# czbd-v0_12.net
KiCad netlist of a schematic drawn in EAGLE
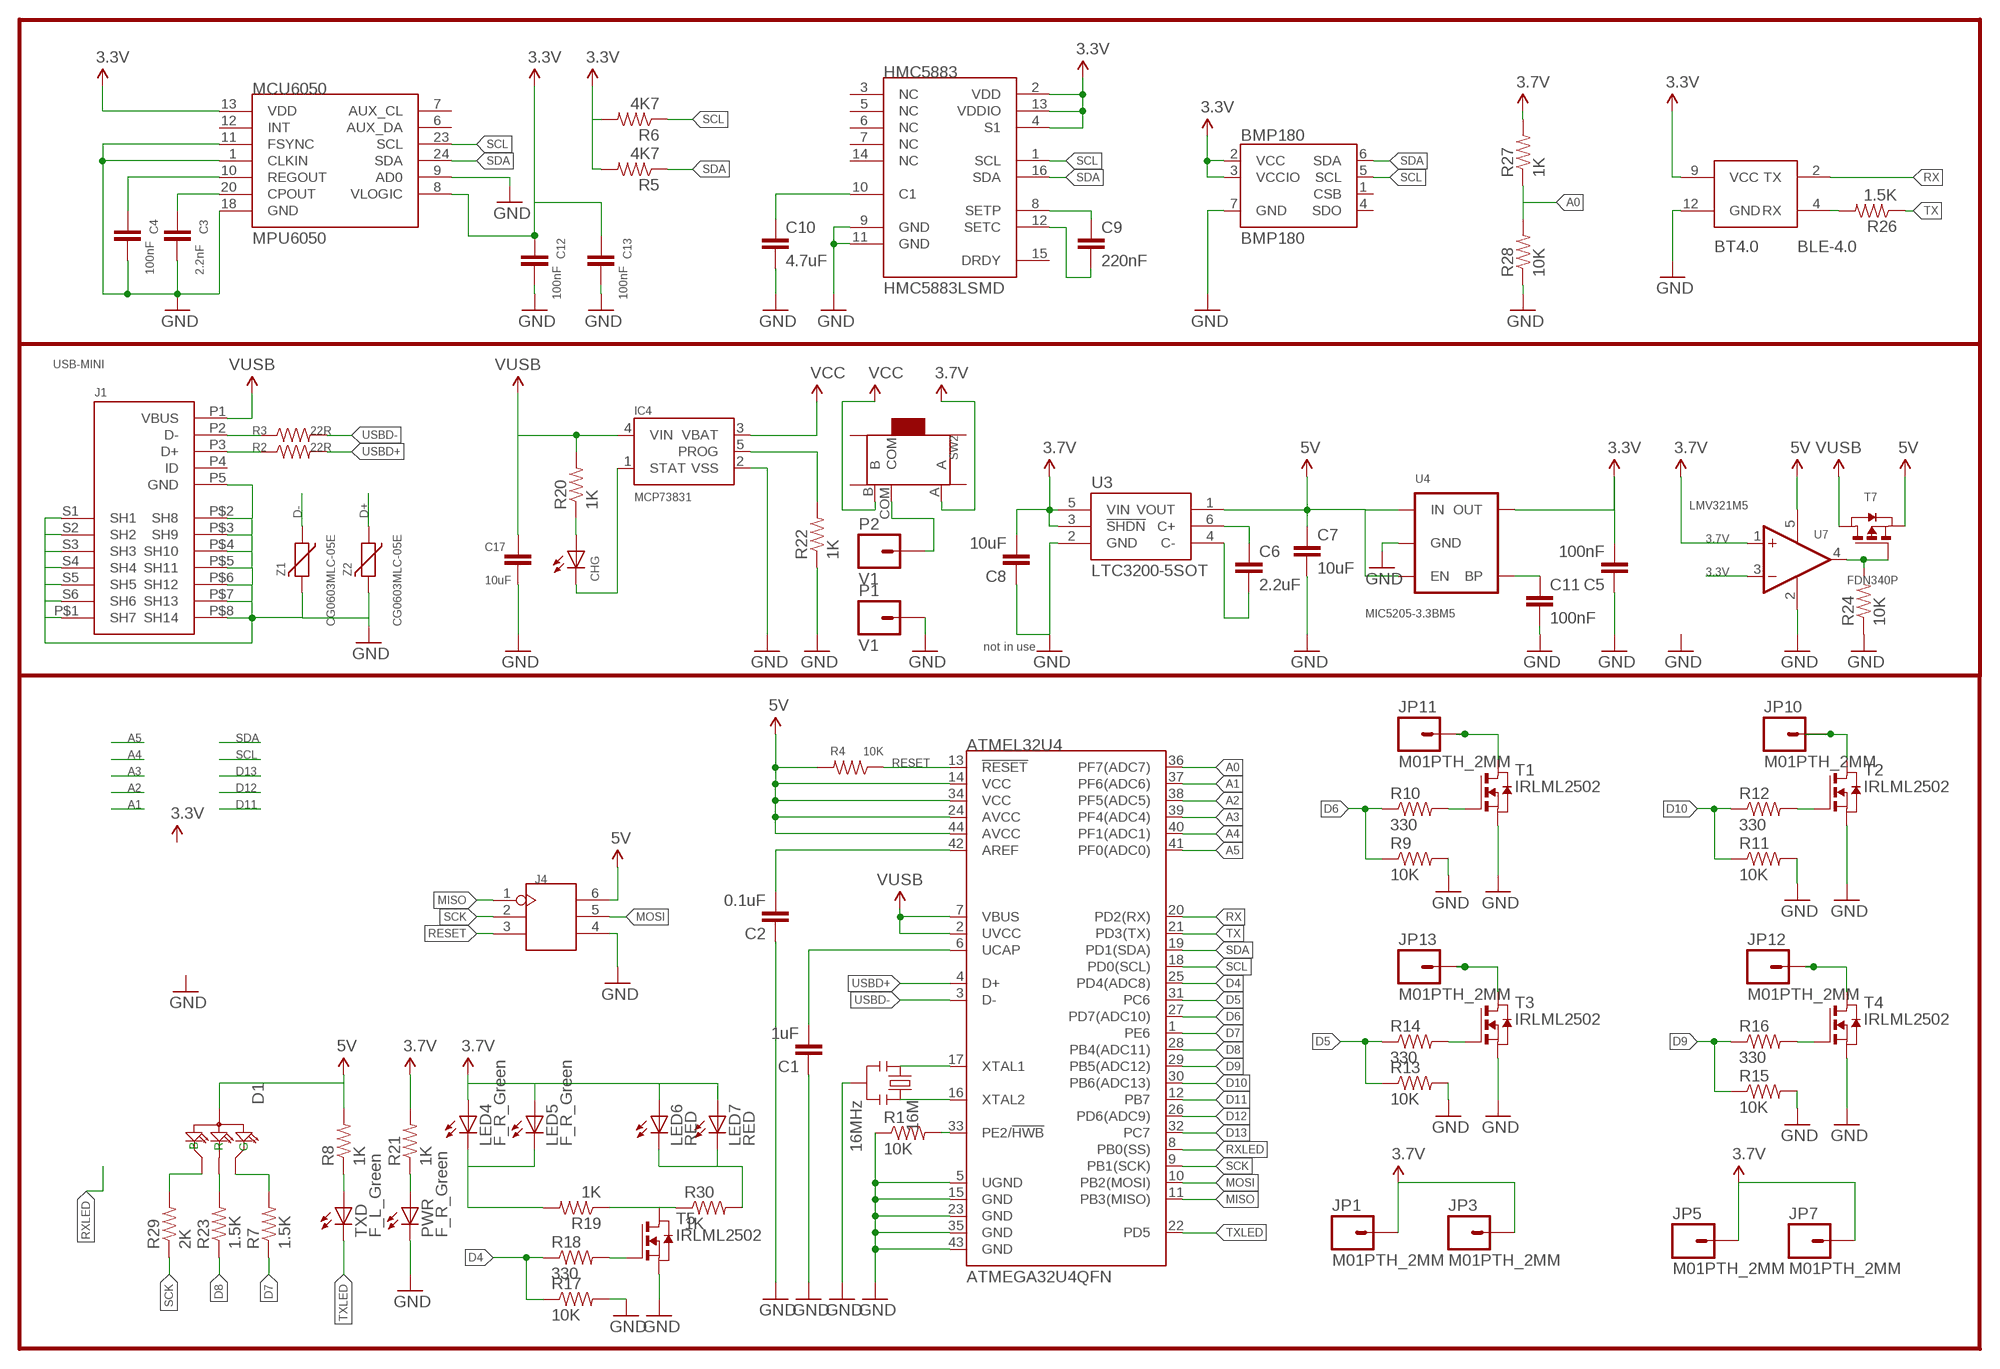
[diagram p0: schematic, sheet 1]

(export (version "E")
  (design (tool "Eeschema 10.0.6"))
  (components
    (comp (ref "16M")
      (value "16MHz")
      (footprint "eagle-import:RESONATOR-SMD")
      (libsource (lib "eagle-import") (part "RESONATOR16MHZ"))
    )
    (comp (ref "ATMEL32U4")
      (value "ATMEGA32U4QFN")
      (footprint "eagle-import:SPARKFUN-DIGITALIC_QFN-44")
      (libsource (lib "eagle-import") (part "ATMEGA32U4QFN"))
    )
    (comp (ref "BMP180")
      (value "BMP180")
      (footprint "eagle-import:BMP180")
      (libsource (lib "eagle-import") (part "BMP180"))
    )
    (comp (ref "BT4.0")
      (value "BLE-4.0")
      (footprint "eagle-import:HEXAIRBOT-HEXNANO_BLUETOOTH_HM11")
      (libsource (lib "eagle-import") (part "HEXAIRBOT-HEXNANO_BLUETOOTH_HM11"))
    )
    (comp (ref "C1")
      (value "1uF")
      (footprint "eagle-import:0402-CAP")
      (libsource (lib "eagle-import") (part "SparkFun-Passives_CAP0402-CAP"))
    )
    (comp (ref "C2")
      (value "0.1uF")
      (footprint "eagle-import:0402-CAP")
      (libsource (lib "eagle-import") (part "SparkFun-Passives_CAP0402-CAP"))
    )
    (comp (ref "C3")
      (value "2.2nF")
      (footprint "eagle-import:0402-CAP")
      (libsource (lib "eagle-import") (part "SparkFun-Passives_CAP0402-CAP"))
    )
    (comp (ref "C4")
      (value "100nF")
      (footprint "eagle-import:0402-CAP")
      (libsource (lib "eagle-import") (part "SparkFun-Passives_CAP0402-CAP"))
    )
    (comp (ref "C5")
      (value "100nF")
      (footprint "eagle-import:0402-CAP")
      (libsource (lib "eagle-import") (part "SparkFun-Passives_CAP0402-CAP"))
    )
    (comp (ref "C6")
      (value "2.2uF")
      (footprint "eagle-import:0402-CAP")
      (libsource (lib "eagle-import") (part "SparkFun-Passives_CAP0402-CAP"))
    )
    (comp (ref "C7")
      (value "10uF")
      (footprint "eagle-import:0402-CAP")
      (libsource (lib "eagle-import") (part "SparkFun-Passives_CAP0402-CAP"))
    )
    (comp (ref "C8")
      (value "10uF")
      (footprint "eagle-import:0805")
      (libsource (lib "eagle-import") (part "SparkFun-Passives_CAP0805"))
    )
    (comp (ref "C9")
      (value "220nF")
      (footprint "eagle-import:0402-CAP")
      (libsource (lib "eagle-import") (part "SparkFun-Passives_CAP0402-CAP"))
    )
    (comp (ref "C10")
      (value "4.7uF")
      (footprint "eagle-import:0402-CAP")
      (libsource (lib "eagle-import") (part "SparkFun-Passives_CAP0402-CAP"))
    )
    (comp (ref "C11")
      (value "100nF")
      (footprint "eagle-import:0402-CAP")
      (libsource (lib "eagle-import") (part "SparkFun-Passives_CAP0402-CAP"))
    )
    (comp (ref "C12")
      (value "100nF")
      (footprint "eagle-import:0402-CAP")
      (libsource (lib "eagle-import") (part "SparkFun-Passives_CAP0402-CAP"))
    )
    (comp (ref "C13")
      (value "100nF")
      (footprint "eagle-import:0402-CAP")
      (libsource (lib "eagle-import") (part "SparkFun-Passives_CAP0402-CAP"))
    )
    (comp (ref "C17")
      (value "10uF")
      (footprint "eagle-import:0805")
      (libsource (lib "eagle-import") (part "CAP0805"))
    )
    (comp (ref "CHG")
      (value "Yellow")
      (footprint "eagle-import:CHIPLED_0603")
      (libsource (lib "eagle-import") (part "LEDCHIPLED_0603"))
    )
    (comp (ref "D1")
      (value "LED-ARGB-4P-1206")
      (footprint "eagle-import:LED-4P-1206-3.0X1.5")
      (libsource (lib "eagle-import") (part "LED-ARGB-4P-1206"))
    )
    (comp (ref "HMC5883")
      (value "HMC5883LSMD")
      (footprint "eagle-import:16LPCC")
      (libsource (lib "eagle-import") (part "HMC5883LSMD"))
    )
    (comp (ref "IC4")
      (value "MCP73831")
      (footprint "eagle-import:SOT23-5")
      (libsource (lib "eagle-import") (part "MCP73831"))
    )
    (comp (ref "J1")
      (value "USB-MINI")
      (footprint "eagle-import:USB_MICRO")
      (libsource (lib "eagle-import") (part "USB-MINI"))
    )
    (comp (ref "J4")
      (value "CONNECTOR_HEADER-2X3P-2.0")
      (footprint "eagle-import:CONNECTOR_2X3P-2.0")
      (libsource (lib "eagle-import") (part "CONNECTOR_HEADER-2X3P-2.0"))
    )
    (comp (ref "JP1")
      (value "M01PTH_2MM")
      (footprint "eagle-import:1X01_2MM")
      (libsource (lib "eagle-import") (part "duinofun-connector_M01PTH_2MM"))
    )
    (comp (ref "JP3")
      (value "M01PTH_2MM")
      (footprint "eagle-import:1X01_2MM")
      (libsource (lib "eagle-import") (part "duinofun-connector_M01PTH_2MM"))
    )
    (comp (ref "JP5")
      (value "M01PTH_2MM")
      (footprint "eagle-import:1X01_2MM")
      (libsource (lib "eagle-import") (part "duinofun-connector_M01PTH_2MM"))
    )
    (comp (ref "JP7")
      (value "M01PTH_2MM")
      (footprint "eagle-import:1X01_2MM")
      (libsource (lib "eagle-import") (part "duinofun-connector_M01PTH_2MM"))
    )
    (comp (ref "JP10")
      (value "M01PTH_2MM")
      (footprint "eagle-import:1X01_2MM")
      (libsource (lib "eagle-import") (part "duinofun-connector_M01PTH_2MM"))
    )
    (comp (ref "JP11")
      (value "M01PTH_2MM")
      (footprint "eagle-import:1X01_2MM")
      (libsource (lib "eagle-import") (part "duinofun-connector_M01PTH_2MM"))
    )
    (comp (ref "JP12")
      (value "M01PTH_2MM")
      (footprint "eagle-import:1X01_2MM")
      (libsource (lib "eagle-import") (part "duinofun-connector_M01PTH_2MM"))
    )
    (comp (ref "JP13")
      (value "M01PTH_2MM")
      (footprint "eagle-import:1X01_2MM")
      (libsource (lib "eagle-import") (part "duinofun-connector_M01PTH_2MM"))
    )
    (comp (ref "LED4")
      (value "F_R_Green")
      (footprint "eagle-import:CHIPLED_0603")
      (libsource (lib "eagle-import") (part "LEDCHIPLED_0603"))
    )
    (comp (ref "LED5")
      (value "F_R_Green")
      (footprint "eagle-import:CHIPLED_0603")
      (libsource (lib "eagle-import") (part "LEDCHIPLED_0603"))
    )
    (comp (ref "LED6")
      (value "RED")
      (footprint "eagle-import:CHIPLED_0603")
      (libsource (lib "eagle-import") (part "LEDCHIPLED_0603"))
    )
    (comp (ref "LED7")
      (value "RED")
      (footprint "eagle-import:CHIPLED_0603")
      (libsource (lib "eagle-import") (part "LEDCHIPLED_0603"))
    )
    (comp (ref "MCU6050")
      (value "MPU6050")
      (footprint "eagle-import:TESTING_QFN-24-4MM2")
      (libsource (lib "eagle-import") (part "TESTING_MPU-6050-1"))
    )
    (comp (ref "P1")
      (value "V1")
      (footprint "eagle-import:1X01")
      (libsource (lib "eagle-import") (part "M01PTH"))
    )
    (comp (ref "P2")
      (value "V1")
      (footprint "eagle-import:1X01")
      (libsource (lib "eagle-import") (part "M01PTH"))
    )
    (comp (ref "PWR")
      (value "F_R_Green")
      (footprint "eagle-import:CHIPLED_0603")
      (libsource (lib "eagle-import") (part "LEDCHIPLED_0603"))
    )
    (comp (ref "R1")
      (value "10K")
      (footprint "eagle-import:0402-RES")
      (libsource (lib "eagle-import") (part "RESISTOR0402-RES"))
    )
    (comp (ref "R2")
      (value "22R")
      (footprint "eagle-import:0402-RES")
      (libsource (lib "eagle-import") (part "RESISTOR0402-RES"))
    )
    (comp (ref "R3")
      (value "22R")
      (footprint "eagle-import:0402-RES")
      (libsource (lib "eagle-import") (part "RESISTOR0402-RES"))
    )
    (comp (ref "R4")
      (value "10K")
      (footprint "eagle-import:0402-RES")
      (libsource (lib "eagle-import") (part "RESISTOR0402-RES"))
    )
    (comp (ref "R5")
      (value "4K7")
      (footprint "eagle-import:0402-RES")
      (libsource (lib "eagle-import") (part "RESISTOR0402-RES"))
    )
    (comp (ref "R6")
      (value "4K7")
      (footprint "eagle-import:0402-RES")
      (libsource (lib "eagle-import") (part "RESISTOR0402-RES"))
    )
    (comp (ref "R7")
      (value "1.5K")
      (footprint "eagle-import:0402-RES")
      (libsource (lib "eagle-import") (part "RESISTOR0402-RES"))
    )
    (comp (ref "R8")
      (value "1K")
      (footprint "eagle-import:0402-RES")
      (libsource (lib "eagle-import") (part "RESISTOR0402-RES"))
    )
    (comp (ref "R9")
      (value "10K")
      (footprint "eagle-import:0402-RES")
      (libsource (lib "eagle-import") (part "RESISTOR0402-RES"))
    )
    (comp (ref "R10")
      (value "330")
      (footprint "eagle-import:0402-RES")
      (libsource (lib "eagle-import") (part "RESISTOR0402-RES"))
    )
    (comp (ref "R11")
      (value "10K")
      (footprint "eagle-import:0402-RES")
      (libsource (lib "eagle-import") (part "RESISTOR0402-RES"))
    )
    (comp (ref "R12")
      (value "330")
      (footprint "eagle-import:0402-RES")
      (libsource (lib "eagle-import") (part "RESISTOR0402-RES"))
    )
    (comp (ref "R13")
      (value "10K")
      (footprint "eagle-import:0402-RES")
      (libsource (lib "eagle-import") (part "RESISTOR0402-RES"))
    )
    (comp (ref "R14")
      (value "330")
      (footprint "eagle-import:0402-RES")
      (libsource (lib "eagle-import") (part "RESISTOR0402-RES"))
    )
    (comp (ref "R15")
      (value "10K")
      (footprint "eagle-import:0402-RES")
      (libsource (lib "eagle-import") (part "RESISTOR0402-RES"))
    )
    (comp (ref "R16")
      (value "330")
      (footprint "eagle-import:0402-RES")
      (libsource (lib "eagle-import") (part "RESISTOR0402-RES"))
    )
    (comp (ref "R17")
      (value "10K")
      (footprint "eagle-import:0402-RES")
      (libsource (lib "eagle-import") (part "RESISTOR0402-RES"))
    )
    (comp (ref "R18")
      (value "330")
      (footprint "eagle-import:0402-RES")
      (libsource (lib "eagle-import") (part "RESISTOR0402-RES"))
    )
    (comp (ref "R19")
      (value "1K")
      (footprint "eagle-import:0402-RES")
      (libsource (lib "eagle-import") (part "RESISTOR0402-RES"))
    )
    (comp (ref "R20")
      (value "1K")
      (footprint "eagle-import:0402-RES")
      (libsource (lib "eagle-import") (part "RESISTOR0402-RES"))
    )
    (comp (ref "R21")
      (value "1K")
      (footprint "eagle-import:0402-RES")
      (libsource (lib "eagle-import") (part "RESISTOR0402-RES"))
    )
    (comp (ref "R22")
      (value "1K")
      (footprint "eagle-import:0402-RES")
      (libsource (lib "eagle-import") (part "RESISTOR0402-RES"))
    )
    (comp (ref "R23")
      (value "1.5K")
      (footprint "eagle-import:0402-RES")
      (libsource (lib "eagle-import") (part "RESISTOR0402-RES"))
    )
    (comp (ref "R24")
      (value "10K")
      (footprint "eagle-import:0402-RES")
      (libsource (lib "eagle-import") (part "RESISTOR0402-RES"))
    )
    (comp (ref "R26")
      (value "1.5K")
      (footprint "eagle-import:0402-RES")
      (libsource (lib "eagle-import") (part "RESISTOR0402-RES"))
    )
    (comp (ref "R27")
      (value "1K")
      (footprint "eagle-import:0402-RES")
      (libsource (lib "eagle-import") (part "RESISTOR0402-RES"))
    )
    (comp (ref "R28")
      (value "10K")
      (footprint "eagle-import:0402-RES")
      (libsource (lib "eagle-import") (part "RESISTOR0402-RES"))
    )
    (comp (ref "R29")
      (value "2K")
      (footprint "eagle-import:0402-RES")
      (libsource (lib "eagle-import") (part "RESISTOR0402-RES"))
    )
    (comp (ref "R30")
      (value "1K")
      (footprint "eagle-import:0402-RES")
      (libsource (lib "eagle-import") (part "RESISTOR0402-RES"))
    )
    (comp (ref "SW2")
      (value "SWITCH-3P-SMD-6.6X2.8")
      (footprint "eagle-import:3P-SMD-2CH-6.6X2.8-REINFORCE")
      (libsource (lib "eagle-import") (part "SWITCH-3P-SMD-6.6X2.8"))
    )
    (comp (ref "T1")
      (value "IRLML2502")
      (footprint "eagle-import:SOT-23")
      (libsource (lib "eagle-import") (part "NMOSSOT23"))
    )
    (comp (ref "T2")
      (value "IRLML2502")
      (footprint "eagle-import:SOT-23")
      (libsource (lib "eagle-import") (part "NMOSSOT23"))
    )
    (comp (ref "T3")
      (value "IRLML2502")
      (footprint "eagle-import:SOT-23")
      (libsource (lib "eagle-import") (part "NMOSSOT23"))
    )
    (comp (ref "T4")
      (value "IRLML2502")
      (footprint "eagle-import:SOT-23")
      (libsource (lib "eagle-import") (part "NMOSSOT23"))
    )
    (comp (ref "T5")
      (value "IRLML2502")
      (footprint "eagle-import:SOT-23")
      (libsource (lib "eagle-import") (part "NMOSSOT23"))
    )
    (comp (ref "T7")
      (value "FDN340P")
      (footprint "eagle-import:SOT23")
      (libsource (lib "eagle-import") (part "FDN340P"))
    )
    (comp (ref "TXD")
      (value "F_L_Green")
      (footprint "eagle-import:CHIPLED_0603")
      (libsource (lib "eagle-import") (part "LEDCHIPLED_0603"))
    )
    (comp (ref "U3")
      (value "LTC3200-5SOT")
      (footprint "eagle-import:SOT23-6")
      (libsource (lib "eagle-import") (part "LTC3200-5SOT"))
    )
    (comp (ref "U4")
      (value "MIC5205-3.3BM5")
      (footprint "eagle-import:SOT23-5")
      (libsource (lib "eagle-import") (part "MIC52053.3V"))
    )
    (comp (ref "U7")
      (value "LMV321M5")
      (footprint "eagle-import:SOT23-5")
      (libsource (lib "eagle-import") (part "LMV321?M5"))
    )
    (comp (ref "Z1")
      (value "CG0603MLC-05E")
      (footprint "eagle-import:CT_CN0603")
      (libsource (lib "eagle-import") (part "VARISTORCN0603"))
    )
    (comp (ref "Z2")
      (value "CG0603MLC-05E")
      (footprint "eagle-import:CT_CN0603")
      (libsource (lib "eagle-import") (part "VARISTORCN0603"))
    )
  )
  (nets
    (net (code "1") (name "/D+") (class "Default")
      (node (ref "J1") (pin "P3") (pinfunction "D+_P3") (pintype "bidirectional"))
      (node (ref "R2") (pin "1") (pinfunction "1_1") (pintype "passive"))
      (node (ref "Z2") (pin "1") (pinfunction "1_1") (pintype "passive"))
    )
    (net (code "2") (name "/D-") (class "Default")
      (node (ref "J1") (pin "P2") (pinfunction "D-_P2") (pintype "bidirectional"))
      (node (ref "R3") (pin "1") (pinfunction "1_1") (pintype "passive"))
      (node (ref "Z1") (pin "1") (pinfunction "1_1") (pintype "passive"))
    )
    (net (code "3") (name "3.3V") (class "Default")
      (node (ref "BMP180") (pin "2") (pinfunction "VCC_2") (pintype "power_in"))
      (node (ref "BMP180") (pin "3") (pinfunction "VCCIO_3") (pintype "power_in"))
      (node (ref "BT4.0") (pin "9") (pinfunction "VCC_9") (pintype "bidirectional"))
      (node (ref "C12") (pin "1") (pinfunction "1_1") (pintype "passive"))
      (node (ref "C13") (pin "1") (pinfunction "1_1") (pintype "passive"))
      (node (ref "C5") (pin "2") (pinfunction "2_2") (pintype "passive"))
      (node (ref "HMC5883") (pin "13") (pinfunction "VDDIO_13") (pintype "bidirectional"))
      (node (ref "HMC5883") (pin "2") (pinfunction "VDD_2") (pintype "bidirectional"))
      (node (ref "HMC5883") (pin "4") (pinfunction "S1_4") (pintype "bidirectional"))
      (node (ref "MCU6050") (pin "13") (pinfunction "VDD_13") (pintype "bidirectional"))
      (node (ref "MCU6050") (pin "8") (pinfunction "VLOGIC_8") (pintype "bidirectional"))
      (node (ref "R5") (pin "2") (pinfunction "2_2") (pintype "passive"))
      (node (ref "R6") (pin "2") (pinfunction "2_2") (pintype "passive"))
      (node (ref "U4") (pin "5") (pinfunction "OUT_5") (pintype "passive"))
      (node (ref "U7") (pin "3") (pinfunction "-IN_3") (pintype "input"))
    )
    (net (code "4") (name "3.7V") (class "Default")
      (node (ref "C8") (pin "2") (pinfunction "2_2") (pintype "passive"))
      (node (ref "JP1") (pin "1") (pinfunction "1_1") (pintype "passive"))
      (node (ref "JP3") (pin "1") (pinfunction "1_1") (pintype "passive"))
      (node (ref "JP5") (pin "1") (pinfunction "1_1") (pintype "passive"))
      (node (ref "JP7") (pin "1") (pinfunction "1_1") (pintype "passive"))
      (node (ref "LED4") (pin "A") (pinfunction "A_A") (pintype "passive"))
      (node (ref "LED5") (pin "A") (pinfunction "A_A") (pintype "passive"))
      (node (ref "LED6") (pin "A") (pinfunction "A_A") (pintype "passive"))
      (node (ref "LED7") (pin "A") (pinfunction "A_A") (pintype "passive"))
      (node (ref "R21") (pin "2") (pinfunction "2_2") (pintype "passive"))
      (node (ref "R27") (pin "2") (pinfunction "2_2") (pintype "passive"))
      (node (ref "SW2") (pin "A") (pinfunction "A_A") (pintype "bidirectional"))
      (node (ref "U3") (pin "3") (pinfunction "~{SHDN}_3") (pintype "bidirectional"))
      (node (ref "U3") (pin "5") (pinfunction "VIN_5") (pintype "bidirectional"))
      (node (ref "U7") (pin "1") (pinfunction "+IN_1") (pintype "input"))
    )
    (net (code "5") (name "5V") (class "Default")
      (node (ref "ATMEL32U4") (pin "14") (pinfunction "VCC_14") (pintype "bidirectional"))
      (node (ref "ATMEL32U4") (pin "24") (pinfunction "AVCC_24") (pintype "bidirectional"))
      (node (ref "ATMEL32U4") (pin "34") (pinfunction "VCC_34") (pintype "bidirectional"))
      (node (ref "ATMEL32U4") (pin "44") (pinfunction "AVCC_44") (pintype "bidirectional"))
      (node (ref "C7") (pin "1") (pinfunction "1_1") (pintype "passive"))
      (node (ref "D1") (pin "2") (pinfunction "+_2") (pintype "bidirectional"))
      (node (ref "J4") (pin "6") (pinfunction "6_6") (pintype "bidirectional"))
      (node (ref "R4") (pin "2") (pinfunction "2_2") (pintype "passive"))
      (node (ref "R8") (pin "2") (pinfunction "2_2") (pintype "passive"))
      (node (ref "T7") (pin "2") (pinfunction "S_2") (pintype "passive"))
      (node (ref "U3") (pin "1") (pinfunction "VOUT_1") (pintype "bidirectional"))
      (node (ref "U4") (pin "1") (pinfunction "IN_1") (pintype "input"))
      (node (ref "U4") (pin "3") (pinfunction "EN_3") (pintype "input"))
      (node (ref "U7") (pin "5") (pinfunction "V+_5") (pintype "power_in"))
    )
    (net (code "6") (name "A0") (class "Default")
      (node (ref "ATMEL32U4") (pin "36") (pinfunction "PF7(ADC7)_36") (pintype "bidirectional"))
      (node (ref "R27") (pin "1") (pinfunction "1_1") (pintype "passive"))
      (node (ref "R28") (pin "2") (pinfunction "2_2") (pintype "passive"))
    )
    (net (code "7") (name "A1") (class "Default")
      (node (ref "ATMEL32U4") (pin "37") (pinfunction "PF6(ADC6)_37") (pintype "bidirectional"))
    )
    (net (code "8") (name "A2") (class "Default")
      (node (ref "ATMEL32U4") (pin "38") (pinfunction "PF5(ADC5)_38") (pintype "bidirectional"))
    )
    (net (code "9") (name "A3") (class "Default")
      (node (ref "ATMEL32U4") (pin "39") (pinfunction "PF4(ADC4)_39") (pintype "bidirectional"))
    )
    (net (code "10") (name "A4") (class "Default")
      (node (ref "ATMEL32U4") (pin "40") (pinfunction "PF1(ADC1)_40") (pintype "bidirectional"))
    )
    (net (code "11") (name "A5") (class "Default")
      (node (ref "ATMEL32U4") (pin "41") (pinfunction "PF0(ADC0)_41") (pintype "bidirectional"))
    )
    (net (code "12") (name "D4") (class "Default")
      (node (ref "ATMEL32U4") (pin "25") (pinfunction "PD4(ADC8)_25") (pintype "bidirectional"))
      (node (ref "R17") (pin "1") (pinfunction "1_1") (pintype "passive"))
      (node (ref "R18") (pin "1") (pinfunction "1_1") (pintype "passive"))
    )
    (net (code "13") (name "D5") (class "Default")
      (node (ref "ATMEL32U4") (pin "31") (pinfunction "PC6_31") (pintype "bidirectional"))
      (node (ref "R13") (pin "1") (pinfunction "1_1") (pintype "passive"))
      (node (ref "R14") (pin "1") (pinfunction "1_1") (pintype "passive"))
    )
    (net (code "14") (name "D6") (class "Default")
      (node (ref "ATMEL32U4") (pin "27") (pinfunction "PD7(ADC10)_27") (pintype "bidirectional"))
      (node (ref "R10") (pin "1") (pinfunction "1_1") (pintype "passive"))
      (node (ref "R9") (pin "1") (pinfunction "1_1") (pintype "passive"))
    )
    (net (code "15") (name "D7") (class "Default")
      (node (ref "ATMEL32U4") (pin "1") (pinfunction "PE6_1") (pintype "bidirectional"))
      (node (ref "R7") (pin "1") (pinfunction "1_1") (pintype "passive"))
    )
    (net (code "16") (name "D8") (class "Default")
      (node (ref "ATMEL32U4") (pin "28") (pinfunction "PB4(ADC11)_28") (pintype "bidirectional"))
      (node (ref "R23") (pin "1") (pinfunction "1_1") (pintype "passive"))
    )
    (net (code "17") (name "D9") (class "Default")
      (node (ref "ATMEL32U4") (pin "29") (pinfunction "PB5(ADC12)_29") (pintype "bidirectional"))
      (node (ref "R15") (pin "1") (pinfunction "1_1") (pintype "passive"))
      (node (ref "R16") (pin "1") (pinfunction "1_1") (pintype "passive"))
    )
    (net (code "18") (name "D10") (class "Default")
      (node (ref "ATMEL32U4") (pin "30") (pinfunction "PB6(ADC13)_30") (pintype "bidirectional"))
      (node (ref "R11") (pin "1") (pinfunction "1_1") (pintype "passive"))
      (node (ref "R12") (pin "1") (pinfunction "1_1") (pintype "passive"))
    )
    (net (code "19") (name "D11") (class "Default")
      (node (ref "ATMEL32U4") (pin "12") (pinfunction "PB7_12") (pintype "bidirectional"))
    )
    (net (code "20") (name "D12") (class "Default")
      (node (ref "ATMEL32U4") (pin "26") (pinfunction "PD6(ADC9)_26") (pintype "bidirectional"))
    )
    (net (code "21") (name "D13") (class "Default")
      (node (ref "ATMEL32U4") (pin "32") (pinfunction "PC7_32") (pintype "bidirectional"))
    )
    (net (code "22") (name "GND") (class "Default")
      (node (ref "16M") (pin "2") (pinfunction "2_2") (pintype "passive"))
      (node (ref "ATMEL32U4") (pin "15") (pinfunction "GND_15") (pintype "bidirectional"))
      (node (ref "ATMEL32U4") (pin "23") (pinfunction "GND_23") (pintype "bidirectional"))
      (node (ref "ATMEL32U4") (pin "35") (pinfunction "GND_35") (pintype "bidirectional"))
      (node (ref "ATMEL32U4") (pin "43") (pinfunction "GND_43") (pintype "bidirectional"))
      (node (ref "ATMEL32U4") (pin "5") (pinfunction "UGND_5") (pintype "bidirectional"))
      (node (ref "BMP180") (pin "7") (pinfunction "GND_7") (pintype "power_in"))
      (node (ref "BT4.0") (pin "12") (pinfunction "GND_12") (pintype "bidirectional"))
      (node (ref "C1") (pin "1") (pinfunction "1_1") (pintype "passive"))
      (node (ref "C10") (pin "2") (pinfunction "2_2") (pintype "passive"))
      (node (ref "C11") (pin "2") (pinfunction "2_2") (pintype "passive"))
      (node (ref "C12") (pin "2") (pinfunction "2_2") (pintype "passive"))
      (node (ref "C13") (pin "2") (pinfunction "2_2") (pintype "passive"))
      (node (ref "C17") (pin "1") (pinfunction "1_1") (pintype "passive"))
      (node (ref "C2") (pin "1") (pinfunction "1_1") (pintype "passive"))
      (node (ref "C3") (pin "2") (pinfunction "2_2") (pintype "passive"))
      (node (ref "C4") (pin "2") (pinfunction "2_2") (pintype "passive"))
      (node (ref "C5") (pin "1") (pinfunction "1_1") (pintype "passive"))
      (node (ref "C7") (pin "2") (pinfunction "2_2") (pintype "passive"))
      (node (ref "C8") (pin "1") (pinfunction "1_1") (pintype "passive"))
      (node (ref "HMC5883") (pin "11") (pinfunction "GND_11") (pintype "bidirectional"))
      (node (ref "HMC5883") (pin "9") (pinfunction "GND_9") (pintype "bidirectional"))
      (node (ref "IC4") (pin "2") (pinfunction "VSS_2") (pintype "power_in"))
      (node (ref "J1") (pin "P$1") (pinfunction "SH7_P$1") (pintype "passive"))
      (node (ref "J1") (pin "P$2") (pinfunction "SH8_P$2") (pintype "passive"))
      (node (ref "J1") (pin "P$3") (pinfunction "SH9_P$3") (pintype "passive"))
      (node (ref "J1") (pin "P$4") (pinfunction "SH10_P$4") (pintype "passive"))
      (node (ref "J1") (pin "P$5") (pinfunction "SH11_P$5") (pintype "passive"))
      (node (ref "J1") (pin "P$6") (pinfunction "SH12_P$6") (pintype "passive"))
      (node (ref "J1") (pin "P$7") (pinfunction "SH13_P$7") (pintype "passive"))
      (node (ref "J1") (pin "P$8") (pinfunction "SH14_P$8") (pintype "passive"))
      (node (ref "J1") (pin "P5") (pinfunction "GND_P5") (pintype "passive"))
      (node (ref "J1") (pin "S1") (pinfunction "SH1_S1") (pintype "passive"))
      (node (ref "J1") (pin "S2") (pinfunction "SH2_S2") (pintype "passive"))
      (node (ref "J1") (pin "S3") (pinfunction "SH3_S3") (pintype "passive"))
      (node (ref "J1") (pin "S4") (pinfunction "SH4_S4") (pintype "passive"))
      (node (ref "J1") (pin "S5") (pinfunction "SH5_S5") (pintype "passive"))
      (node (ref "J1") (pin "S6") (pinfunction "SH6_S6") (pintype "passive"))
      (node (ref "J4") (pin "4") (pinfunction "4_4") (pintype "bidirectional"))
      (node (ref "MCU6050") (pin "1") (pinfunction "CLKIN_1") (pintype "bidirectional"))
      (node (ref "MCU6050") (pin "11") (pinfunction "FSYNC_11") (pintype "bidirectional"))
      (node (ref "MCU6050") (pin "18") (pinfunction "GND_18") (pintype "bidirectional"))
      (node (ref "MCU6050") (pin "9") (pinfunction "AD0_9") (pintype "bidirectional"))
      (node (ref "P1") (pin "1") (pinfunction "1_1") (pintype "passive"))
      (node (ref "PWR") (pin "C") (pinfunction "C_C") (pintype "passive"))
      (node (ref "R1") (pin "1") (pinfunction "1_1") (pintype "passive"))
      (node (ref "R11") (pin "2") (pinfunction "2_2") (pintype "passive"))
      (node (ref "R13") (pin "2") (pinfunction "2_2") (pintype "passive"))
      (node (ref "R15") (pin "2") (pinfunction "2_2") (pintype "passive"))
      (node (ref "R17") (pin "2") (pinfunction "2_2") (pintype "passive"))
      (node (ref "R22") (pin "1") (pinfunction "1_1") (pintype "passive"))
      (node (ref "R24") (pin "1") (pinfunction "1_1") (pintype "passive"))
      (node (ref "R28") (pin "1") (pinfunction "1_1") (pintype "passive"))
      (node (ref "R9") (pin "2") (pinfunction "2_2") (pintype "passive"))
      (node (ref "T1") (pin "2") (pinfunction "S_2") (pintype "passive"))
      (node (ref "T2") (pin "2") (pinfunction "S_2") (pintype "passive"))
      (node (ref "T3") (pin "2") (pinfunction "S_2") (pintype "passive"))
      (node (ref "T4") (pin "2") (pinfunction "S_2") (pintype "passive"))
      (node (ref "T5") (pin "2") (pinfunction "S_2") (pintype "passive"))
      (node (ref "U3") (pin "2") (pinfunction "GND_2") (pintype "bidirectional"))
      (node (ref "U4") (pin "2") (pinfunction "GND_2") (pintype "input"))
      (node (ref "U7") (pin "2") (pinfunction "V-_2") (pintype "power_in"))
      (node (ref "Z1") (pin "2") (pinfunction "2_2") (pintype "passive"))
      (node (ref "Z2") (pin "2") (pinfunction "2_2") (pintype "passive"))
    )
    (net (code "23") (name "MISO") (class "Default")
      (node (ref "ATMEL32U4") (pin "11") (pinfunction "PB3(MISO)_11") (pintype "bidirectional"))
      (node (ref "J4") (pin "1") (pinfunction "1_1") (pintype "bidirectional"))
    )
    (net (code "24") (name "MOSI") (class "Default")
      (node (ref "ATMEL32U4") (pin "10") (pinfunction "PB2(MOSI)_10") (pintype "bidirectional"))
      (node (ref "J4") (pin "5") (pinfunction "5_5") (pintype "bidirectional"))
    )
    (net (code "25") (name "Net-(ATMEL32U4-AREF)") (class "Default")
      (node (ref "ATMEL32U4") (pin "42") (pinfunction "AREF_42") (pintype "bidirectional"))
      (node (ref "C2") (pin "2") (pinfunction "2_2") (pintype "passive"))
    )
    (net (code "26") (name "Net-(ATMEL32U4-PE2{slash}~{HWB})") (class "Default")
      (node (ref "ATMEL32U4") (pin "33") (pinfunction "PE2/~{HWB}_33") (pintype "bidirectional"))
      (node (ref "R1") (pin "2") (pinfunction "2_2") (pintype "passive"))
    )
    (net (code "27") (name "Net-(ATMEL32U4-UCAP)") (class "Default")
      (node (ref "ATMEL32U4") (pin "6") (pinfunction "UCAP_6") (pintype "bidirectional"))
      (node (ref "C1") (pin "2") (pinfunction "2_2") (pintype "passive"))
    )
    (net (code "28") (name "Net-(ATMEL32U4-XTAL1)") (class "Default")
      (node (ref "16M") (pin "1") (pinfunction "1_1") (pintype "passive"))
      (node (ref "ATMEL32U4") (pin "17") (pinfunction "XTAL1_17") (pintype "bidirectional"))
    )
    (net (code "29") (name "Net-(ATMEL32U4-XTAL2)") (class "Default")
      (node (ref "16M") (pin "3") (pinfunction "3_3") (pintype "passive"))
      (node (ref "ATMEL32U4") (pin "16") (pinfunction "XTAL2_16") (pintype "bidirectional"))
    )
    (net (code "30") (name "Net-(BT4.0-RX)") (class "Default")
      (node (ref "BT4.0") (pin "4") (pinfunction "RX_4") (pintype "bidirectional"))
      (node (ref "R26") (pin "2") (pinfunction "2_2") (pintype "passive"))
    )
    (net (code "31") (name "Net-(CHG-PadA)") (class "Default")
      (node (ref "CHG") (pin "A") (pinfunction "A_A") (pintype "passive"))
      (node (ref "R20") (pin "1") (pinfunction "1_1") (pintype "passive"))
    )
    (net (code "32") (name "Net-(D1-B)") (class "Default")
      (node (ref "D1") (pin "1") (pinfunction "B_1") (pintype "bidirectional"))
      (node (ref "R29") (pin "2") (pinfunction "2_2") (pintype "passive"))
    )
    (net (code "33") (name "Net-(D1-G)") (class "Default")
      (node (ref "D1") (pin "3") (pinfunction "G_3") (pintype "bidirectional"))
      (node (ref "R7") (pin "2") (pinfunction "2_2") (pintype "passive"))
    )
    (net (code "34") (name "Net-(D1-R)") (class "Default")
      (node (ref "D1") (pin "4") (pinfunction "R_4") (pintype "bidirectional"))
      (node (ref "R23") (pin "2") (pinfunction "2_2") (pintype "passive"))
    )
    (net (code "35") (name "Net-(HMC5883-C1)") (class "Default")
      (node (ref "C10") (pin "1") (pinfunction "1_1") (pintype "passive"))
      (node (ref "HMC5883") (pin "10") (pinfunction "C1_10") (pintype "bidirectional"))
    )
    (net (code "36") (name "Net-(HMC5883-SETC)") (class "Default")
      (node (ref "C9") (pin "2") (pinfunction "2_2") (pintype "passive"))
      (node (ref "HMC5883") (pin "12") (pinfunction "SETC_12") (pintype "bidirectional"))
    )
    (net (code "37") (name "Net-(HMC5883-SETP)") (class "Default")
      (node (ref "C9") (pin "1") (pinfunction "1_1") (pintype "passive"))
      (node (ref "HMC5883") (pin "8") (pinfunction "SETP_8") (pintype "bidirectional"))
    )
    (net (code "38") (name "Net-(IC4-PROG)") (class "Default")
      (node (ref "IC4") (pin "5") (pinfunction "PROG_5") (pintype "input"))
      (node (ref "R22") (pin "2") (pinfunction "2_2") (pintype "passive"))
    )
    (net (code "39") (name "Net-(IC4-STAT)") (class "Default")
      (node (ref "CHG") (pin "C") (pinfunction "C_C") (pintype "passive"))
      (node (ref "IC4") (pin "1") (pinfunction "STAT_1") (pintype "output"))
    )
    (net (code "40") (name "Net-(LED4-PadC)") (class "Default")
      (node (ref "LED4") (pin "C") (pinfunction "C_C") (pintype "passive"))
      (node (ref "LED5") (pin "C") (pinfunction "C_C") (pintype "passive"))
      (node (ref "R19") (pin "2") (pinfunction "2_2") (pintype "passive"))
    )
    (net (code "41") (name "Net-(LED6-PadC)") (class "Default")
      (node (ref "LED6") (pin "C") (pinfunction "C_C") (pintype "passive"))
      (node (ref "LED7") (pin "C") (pinfunction "C_C") (pintype "passive"))
      (node (ref "R30") (pin "2") (pinfunction "2_2") (pintype "passive"))
    )
    (net (code "42") (name "Net-(MCU6050-CPOUT)") (class "Default")
      (node (ref "C3") (pin "1") (pinfunction "1_1") (pintype "passive"))
      (node (ref "MCU6050") (pin "20") (pinfunction "CPOUT_20") (pintype "bidirectional"))
    )
    (net (code "43") (name "Net-(MCU6050-REGOUT)") (class "Default")
      (node (ref "C4") (pin "1") (pinfunction "1_1") (pintype "passive"))
      (node (ref "MCU6050") (pin "10") (pinfunction "REGOUT_10") (pintype "bidirectional"))
    )
    (net (code "44") (name "Net-(P2-Pad1)") (class "Default")
      (node (ref "P2") (pin "1") (pinfunction "1_1") (pintype "passive"))
      (node (ref "SW2") (pin "COM") (pinfunction "COM_COM") (pintype "bidirectional"))
    )
    (net (code "45") (name "Net-(PWR-PadA)") (class "Default")
      (node (ref "PWR") (pin "A") (pinfunction "A_A") (pintype "passive"))
      (node (ref "R21") (pin "1") (pinfunction "1_1") (pintype "passive"))
    )
    (net (code "46") (name "Net-(R8-Pad1)") (class "Default")
      (node (ref "R8") (pin "1") (pinfunction "1_1") (pintype "passive"))
      (node (ref "TXD") (pin "A") (pinfunction "A_A") (pintype "passive"))
    )
    (net (code "47") (name "Net-(T1-D)") (class "Default")
      (node (ref "JP11") (pin "1") (pinfunction "1_1") (pintype "passive"))
      (node (ref "T1") (pin "1") (pinfunction "D_1") (pintype "passive"))
    )
    (net (code "48") (name "Net-(T1-G)") (class "Default")
      (node (ref "R10") (pin "2") (pinfunction "2_2") (pintype "passive"))
      (node (ref "T1") (pin "3") (pinfunction "G_3") (pintype "passive"))
    )
    (net (code "49") (name "Net-(T2-D)") (class "Default")
      (node (ref "JP10") (pin "1") (pinfunction "1_1") (pintype "passive"))
      (node (ref "T2") (pin "1") (pinfunction "D_1") (pintype "passive"))
    )
    (net (code "50") (name "Net-(T2-G)") (class "Default")
      (node (ref "R12") (pin "2") (pinfunction "2_2") (pintype "passive"))
      (node (ref "T2") (pin "3") (pinfunction "G_3") (pintype "passive"))
    )
    (net (code "51") (name "Net-(T3-D)") (class "Default")
      (node (ref "JP13") (pin "1") (pinfunction "1_1") (pintype "passive"))
      (node (ref "T3") (pin "1") (pinfunction "D_1") (pintype "passive"))
    )
    (net (code "52") (name "Net-(T3-G)") (class "Default")
      (node (ref "R14") (pin "2") (pinfunction "2_2") (pintype "passive"))
      (node (ref "T3") (pin "3") (pinfunction "G_3") (pintype "passive"))
    )
    (net (code "53") (name "Net-(T4-D)") (class "Default")
      (node (ref "JP12") (pin "1") (pinfunction "1_1") (pintype "passive"))
      (node (ref "T4") (pin "1") (pinfunction "D_1") (pintype "passive"))
    )
    (net (code "54") (name "Net-(T4-G)") (class "Default")
      (node (ref "R16") (pin "2") (pinfunction "2_2") (pintype "passive"))
      (node (ref "T4") (pin "3") (pinfunction "G_3") (pintype "passive"))
    )
    (net (code "55") (name "Net-(T5-D)") (class "Default")
      (node (ref "R19") (pin "1") (pinfunction "1_1") (pintype "passive"))
      (node (ref "R30") (pin "1") (pinfunction "1_1") (pintype "passive"))
      (node (ref "T5") (pin "1") (pinfunction "D_1") (pintype "passive"))
    )
    (net (code "56") (name "Net-(T5-G)") (class "Default")
      (node (ref "R18") (pin "2") (pinfunction "2_2") (pintype "passive"))
      (node (ref "T5") (pin "3") (pinfunction "G_3") (pintype "passive"))
    )
    (net (code "57") (name "Net-(T7-G)") (class "Default")
      (node (ref "R24") (pin "2") (pinfunction "2_2") (pintype "passive"))
      (node (ref "T7") (pin "3") (pinfunction "G_3") (pintype "passive"))
      (node (ref "U7") (pin "4") (pinfunction "OUT_4") (pintype "output"))
    )
    (net (code "58") (name "Net-(U3-C+)") (class "Default")
      (node (ref "C6") (pin "1") (pinfunction "1_1") (pintype "passive"))
      (node (ref "U3") (pin "6") (pinfunction "C+_6") (pintype "bidirectional"))
    )
    (net (code "59") (name "Net-(U3-C-)") (class "Default")
      (node (ref "C6") (pin "2") (pinfunction "2_2") (pintype "passive"))
      (node (ref "U3") (pin "4") (pinfunction "C-_4") (pintype "bidirectional"))
    )
    (net (code "60") (name "Net-(U4-BP)") (class "Default")
      (node (ref "C11") (pin "1") (pinfunction "1_1") (pintype "passive"))
      (node (ref "U4") (pin "4") (pinfunction "BP_4") (pintype "input"))
    )
    (net (code "61") (name "RESET") (class "Default")
      (node (ref "ATMEL32U4") (pin "13") (pinfunction "~{RESET}_13") (pintype "bidirectional"))
      (node (ref "J4") (pin "3") (pinfunction "3_3") (pintype "bidirectional"))
      (node (ref "R4") (pin "1") (pinfunction "1_1") (pintype "passive"))
    )
    (net (code "62") (name "RX") (class "Default")
      (node (ref "ATMEL32U4") (pin "20") (pinfunction "PD2(RX)_20") (pintype "bidirectional"))
      (node (ref "BT4.0") (pin "2") (pinfunction "TX_2") (pintype "bidirectional"))
    )
    (net (code "63") (name "RXLED") (class "Default")
      (node (ref "ATMEL32U4") (pin "8") (pinfunction "PB0(SS)_8") (pintype "bidirectional"))
    )
    (net (code "64") (name "SCK") (class "Default")
      (node (ref "ATMEL32U4") (pin "9") (pinfunction "PB1(SCK)_9") (pintype "bidirectional"))
      (node (ref "J4") (pin "2") (pinfunction "2_2") (pintype "bidirectional"))
      (node (ref "R29") (pin "1") (pinfunction "1_1") (pintype "passive"))
    )
    (net (code "65") (name "SCL") (class "Default")
      (node (ref "ATMEL32U4") (pin "18") (pinfunction "PD0(SCL)_18") (pintype "bidirectional"))
      (node (ref "BMP180") (pin "5") (pinfunction "SCL_5") (pintype "input"))
      (node (ref "HMC5883") (pin "1") (pinfunction "SCL_1") (pintype "bidirectional"))
      (node (ref "MCU6050") (pin "23") (pinfunction "SCL_23") (pintype "bidirectional"))
      (node (ref "R6") (pin "1") (pinfunction "1_1") (pintype "passive"))
    )
    (net (code "66") (name "SDA") (class "Default")
      (node (ref "ATMEL32U4") (pin "19") (pinfunction "PD1(SDA)_19") (pintype "bidirectional"))
      (node (ref "BMP180") (pin "6") (pinfunction "SDA_6") (pintype "bidirectional"))
      (node (ref "HMC5883") (pin "16") (pinfunction "SDA_16") (pintype "bidirectional"))
      (node (ref "MCU6050") (pin "24") (pinfunction "SDA_24") (pintype "bidirectional"))
      (node (ref "R5") (pin "1") (pinfunction "1_1") (pintype "passive"))
    )
    (net (code "67") (name "TX") (class "Default")
      (node (ref "ATMEL32U4") (pin "21") (pinfunction "PD3(TX)_21") (pintype "bidirectional"))
      (node (ref "R26") (pin "1") (pinfunction "1_1") (pintype "passive"))
    )
    (net (code "68") (name "TXLED") (class "Default")
      (node (ref "ATMEL32U4") (pin "22") (pinfunction "PD5_22") (pintype "bidirectional"))
      (node (ref "TXD") (pin "C") (pinfunction "C_C") (pintype "passive"))
    )
    (net (code "69") (name "USBD+") (class "Default")
      (node (ref "ATMEL32U4") (pin "4") (pinfunction "D+_4") (pintype "bidirectional"))
      (node (ref "R2") (pin "2") (pinfunction "2_2") (pintype "passive"))
    )
    (net (code "70") (name "USBD-") (class "Default")
      (node (ref "ATMEL32U4") (pin "3") (pinfunction "D-_3") (pintype "bidirectional"))
      (node (ref "R3") (pin "2") (pinfunction "2_2") (pintype "passive"))
    )
    (net (code "71") (name "VCC") (class "Default")
      (node (ref "IC4") (pin "3") (pinfunction "VBAT_3") (pintype "power_in"))
      (node (ref "SW2") (pin "B") (pinfunction "B_B") (pintype "bidirectional"))
    )
    (net (code "72") (name "VUSB") (class "Default")
      (node (ref "ATMEL32U4") (pin "2") (pinfunction "UVCC_2") (pintype "bidirectional"))
      (node (ref "ATMEL32U4") (pin "7") (pinfunction "VBUS_7") (pintype "bidirectional"))
      (node (ref "C17") (pin "2") (pinfunction "2_2") (pintype "passive"))
      (node (ref "IC4") (pin "4") (pinfunction "VIN_4") (pintype "power_in"))
      (node (ref "J1") (pin "P1") (pinfunction "VBUS_P1") (pintype "power_in"))
      (node (ref "R20") (pin "2") (pinfunction "2_2") (pintype "passive"))
      (node (ref "T7") (pin "1") (pinfunction "D_1") (pintype "passive"))
    )
    (net (code "73") (name "unconnected-(BMP180-CSB-Pad1)") (class "Default")
      (node (ref "BMP180") (pin "1") (pinfunction "CSB_1") (pintype "output"))
    )
    (net (code "74") (name "unconnected-(BMP180-SDO-Pad4)") (class "Default")
      (node (ref "BMP180") (pin "4") (pinfunction "SDO_4") (pintype "input"))
    )
    (net (code "75") (name "unconnected-(HMC5883-DRDY-Pad15)") (class "Default")
      (node (ref "HMC5883") (pin "15") (pinfunction "DRDY_15") (pintype "bidirectional"))
    )
    (net (code "76") (name "unconnected-(HMC5883-NC-Pad3)") (class "Default")
      (node (ref "HMC5883") (pin "3") (pinfunction "NC_3") (pintype "bidirectional"))
    )
    (net (code "77") (name "unconnected-(HMC5883-NC-Pad5)") (class "Default")
      (node (ref "HMC5883") (pin "5") (pinfunction "NC_5") (pintype "bidirectional"))
    )
    (net (code "78") (name "unconnected-(HMC5883-NC-Pad6)") (class "Default")
      (node (ref "HMC5883") (pin "6") (pinfunction "NC_6") (pintype "bidirectional"))
    )
    (net (code "79") (name "unconnected-(HMC5883-NC-Pad7)") (class "Default")
      (node (ref "HMC5883") (pin "7") (pinfunction "NC_7") (pintype "bidirectional"))
    )
    (net (code "80") (name "unconnected-(HMC5883-NC-Pad14)") (class "Default")
      (node (ref "HMC5883") (pin "14") (pinfunction "NC_14") (pintype "bidirectional"))
    )
    (net (code "81") (name "unconnected-(J1-ID-PadP4)") (class "Default")
      (node (ref "J1") (pin "P4") (pinfunction "ID_P4") (pintype "bidirectional"))
    )
    (net (code "82") (name "unconnected-(MCU6050-AUX_CL-Pad7)") (class "Default")
      (node (ref "MCU6050") (pin "7") (pinfunction "AUX_CL_7") (pintype "bidirectional"))
    )
    (net (code "83") (name "unconnected-(MCU6050-AUX_DA-Pad6)") (class "Default")
      (node (ref "MCU6050") (pin "6") (pinfunction "AUX_DA_6") (pintype "bidirectional"))
    )
    (net (code "84") (name "unconnected-(MCU6050-INT-Pad12)") (class "Default")
      (node (ref "MCU6050") (pin "12") (pinfunction "INT_12") (pintype "bidirectional"))
    )
    (net (code "85") (name "unconnected-(SW2-PadSS1)") (class "Default")
      (node (ref "SW2") (pin "SS1") (pinfunction "SS1_SS1") (pintype "bidirectional"))
    )
    (net (code "86") (name "unconnected-(SW2-PadSS2)") (class "Default")
      (node (ref "SW2") (pin "SS2") (pinfunction "SS2_SS2") (pintype "bidirectional"))
    )
    (net (code "87") (name "unconnected-(SW2-PadSS3)") (class "Default")
      (node (ref "SW2") (pin "SS3") (pinfunction "SS3_SS3") (pintype "bidirectional"))
    )
    (net (code "88") (name "unconnected-(SW2-PadSS4)") (class "Default")
      (node (ref "SW2") (pin "SS4") (pinfunction "SS4_SS4") (pintype "bidirectional"))
    )
  )
)
